# strip.net
KiCad netlist of a schematic drawn in EAGLE
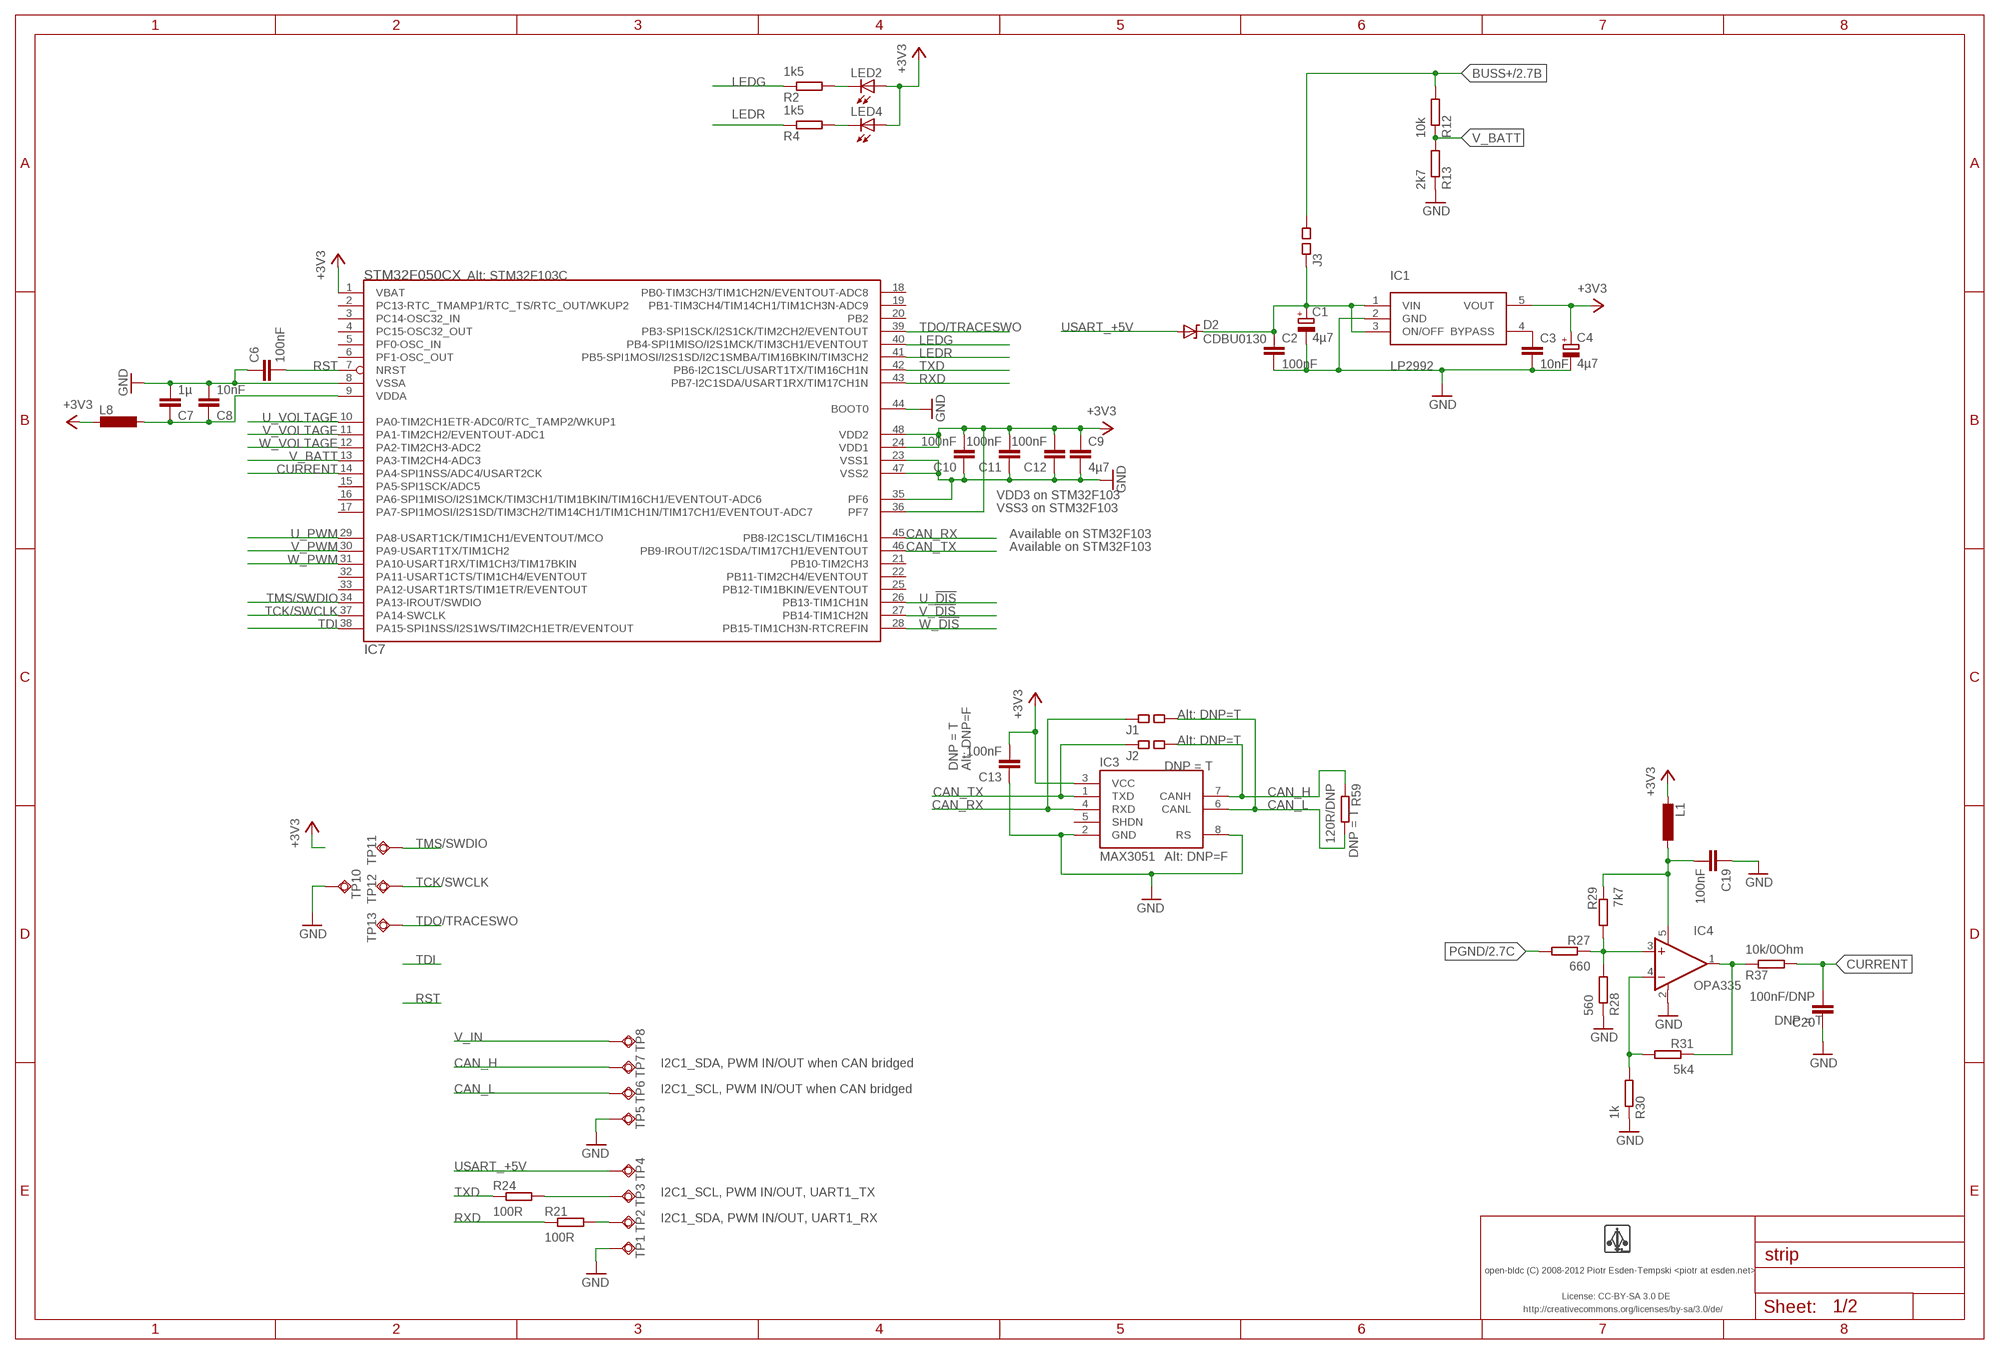
[diagram p0: schematic, sheet 1]
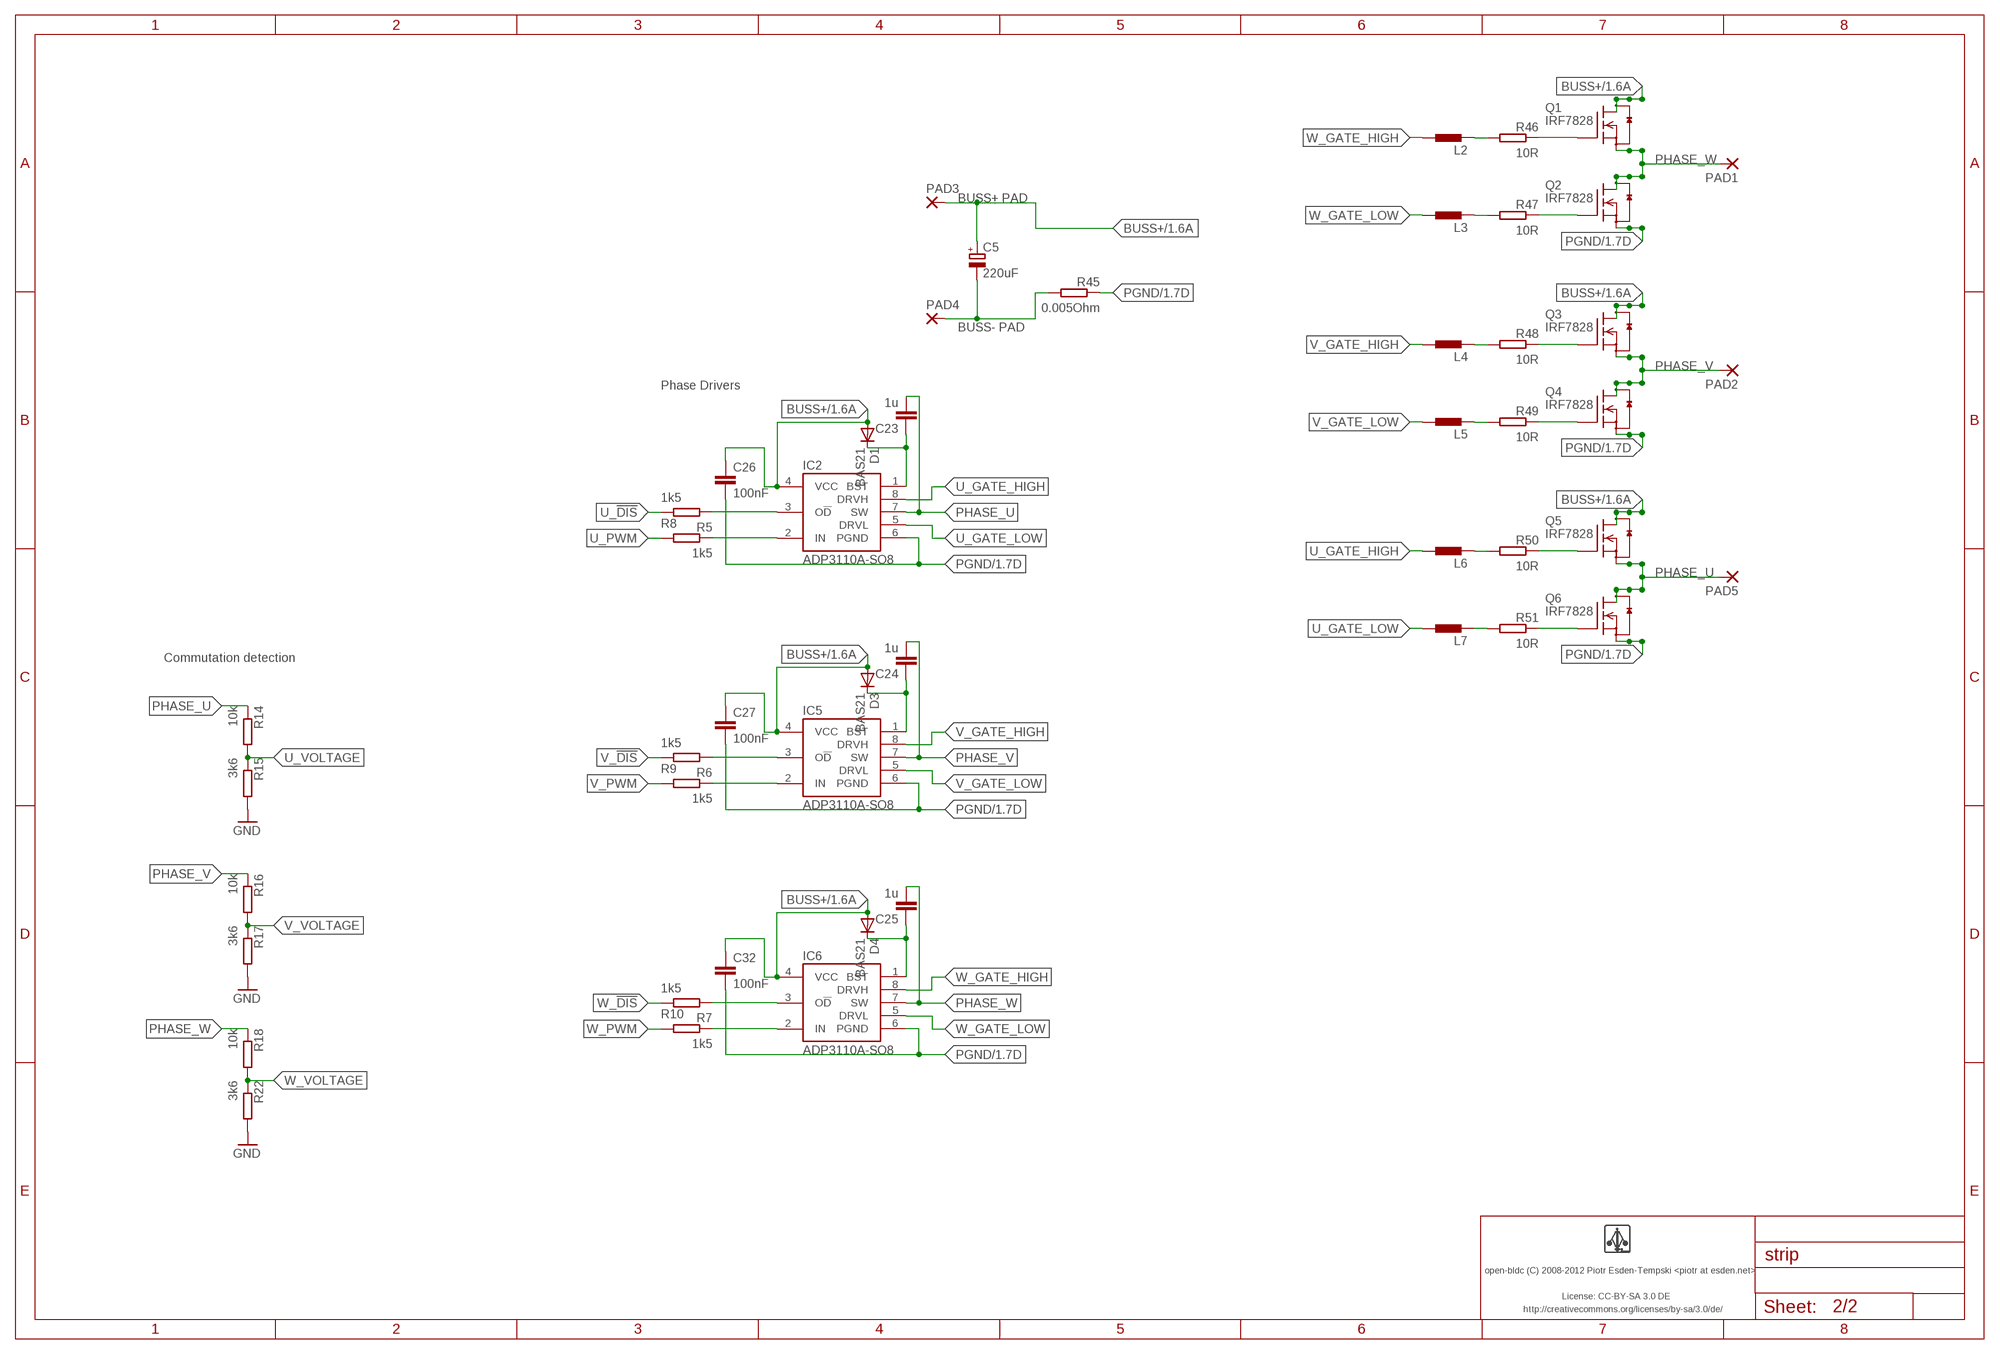
[diagram p1: schematic, sheet 2]

(export (version "E")
  (design (tool "Eeschema 10.0.6"))
  (components
    (comp (ref "C5")
      (value "220uF")
      (footprint "eagle-import:7343_D")
      (fields (field (name "PARTNO") "cap-tan-D-220u-16v"))
      (libsource (lib "eagle-import") (part "CAPACITOR-POLD"))
    )
    (comp (ref "C23")
      (value "1u")
      (footprint "eagle-import:0603-CAP")
      (fields (field (name "PARTNO") "cap-tan-0603-1u"))
      (libsource (lib "eagle-import") (part "CAPACITOR-0603"))
    )
    (comp (ref "C24")
      (value "1u")
      (footprint "eagle-import:0603-CAP")
      (fields (field (name "PARTNO") "cap-tan-0603-1u"))
      (libsource (lib "eagle-import") (part "CAPACITOR-0603"))
    )
    (comp (ref "C25")
      (value "1u")
      (footprint "eagle-import:0603-CAP")
      (fields (field (name "PARTNO") "cap-tan-0603-1u"))
      (libsource (lib "eagle-import") (part "CAPACITOR-0603"))
    )
    (comp (ref "C26")
      (value "100nF")
      (footprint "eagle-import:0402-CAP")
      (fields (field (name "PARTNO") "cap-cer-0402-100n"))
      (libsource (lib "eagle-import") (part "CAPACITOR-0402"))
    )
    (comp (ref "C27")
      (value "100nF")
      (footprint "eagle-import:0402-CAP")
      (fields (field (name "PARTNO") "cap-cer-0402-100n"))
      (libsource (lib "eagle-import") (part "CAPACITOR-0402"))
    )
    (comp (ref "C32")
      (value "100nF")
      (footprint "eagle-import:0402-CAP")
      (fields (field (name "PARTNO") "cap-cer-0402-100n"))
      (libsource (lib "eagle-import") (part "CAPACITOR-0402"))
    )
    (comp (ref "D1")
      (value "BAS21")
      (footprint "eagle-import:SOD-123-DIO")
      (fields (field (name "PARTNO") "diode-sod-123"))
      (libsource (lib "eagle-import") (part "DIODE-SOD-123"))
    )
    (comp (ref "D3")
      (value "BAS21")
      (footprint "eagle-import:SOD-123-DIO")
      (fields (field (name "PARTNO") "diode-sod-123"))
      (libsource (lib "eagle-import") (part "DIODE-SOD-123"))
    )
    (comp (ref "D4")
      (value "BAS21")
      (footprint "eagle-import:SOD-123-DIO")
      (fields (field (name "PARTNO") "diode-sod-123"))
      (libsource (lib "eagle-import") (part "DIODE-SOD-123"))
    )
    (comp (ref "IC2")
      (value "ADP3110A-SO8")
      (footprint "eagle-import:SO8")
      (fields (field (name "PARTNO") "ic-so8-mosfet-driver-buck"))
      (libsource (lib "eagle-import") (part "ADP3110A-SO8"))
    )
    (comp (ref "IC5")
      (value "ADP3110A-SO8")
      (footprint "eagle-import:SO8")
      (fields (field (name "PARTNO") "ic-so8-mosfet-driver-buck"))
      (libsource (lib "eagle-import") (part "ADP3110A-SO8"))
    )
    (comp (ref "IC6")
      (value "ADP3110A-SO8")
      (footprint "eagle-import:SO8")
      (fields (field (name "PARTNO") "ic-so8-mosfet-driver-buck"))
      (libsource (lib "eagle-import") (part "ADP3110A-SO8"))
    )
    (comp (ref "L2")
      (value "INDUCTOR-0402")
      (footprint "eagle-import:0402-IND")
      (fields (field (name "PARTNO") "res-0402-0"))
      (libsource (lib "eagle-import") (part "INDUCTOR-0402"))
    )
    (comp (ref "L3")
      (value "INDUCTOR-0402")
      (footprint "eagle-import:0402-IND")
      (fields (field (name "PARTNO") "res-0402-0"))
      (libsource (lib "eagle-import") (part "INDUCTOR-0402"))
    )
    (comp (ref "L4")
      (value "INDUCTOR-0402")
      (footprint "eagle-import:0402-IND")
      (fields (field (name "PARTNO") "res-0402-0"))
      (libsource (lib "eagle-import") (part "INDUCTOR-0402"))
    )
    (comp (ref "L5")
      (value "INDUCTOR-0402")
      (footprint "eagle-import:0402-IND")
      (fields (field (name "PARTNO") "res-0402-0"))
      (libsource (lib "eagle-import") (part "INDUCTOR-0402"))
    )
    (comp (ref "L6")
      (value "INDUCTOR-0402")
      (footprint "eagle-import:0402-IND")
      (fields (field (name "PARTNO") "res-0402-0"))
      (libsource (lib "eagle-import") (part "INDUCTOR-0402"))
    )
    (comp (ref "L7")
      (value "INDUCTOR-0402")
      (footprint "eagle-import:0402-IND")
      (fields (field (name "PARTNO") "res-0402-0"))
      (libsource (lib "eagle-import") (part "INDUCTOR-0402"))
    )
    (comp (ref "PAD1")
      (value "SMD5")
      (footprint "eagle-import:SMD2,54-5,08")
      (libsource (lib "eagle-import") (part "SMD5"))
    )
    (comp (ref "PAD2")
      (value "SMD5")
      (footprint "eagle-import:SMD2,54-5,08")
      (libsource (lib "eagle-import") (part "SMD5"))
    )
    (comp (ref "PAD3")
      (value "SMD5")
      (footprint "eagle-import:SMD2,54-5,08")
      (libsource (lib "eagle-import") (part "SMD5"))
    )
    (comp (ref "PAD4")
      (value "SMD5")
      (footprint "eagle-import:SMD2,54-5,08")
      (libsource (lib "eagle-import") (part "SMD5"))
    )
    (comp (ref "PAD5")
      (value "SMD5")
      (footprint "eagle-import:SMD2,54-5,08")
      (libsource (lib "eagle-import") (part "SMD5"))
    )
    (comp (ref "Q1")
      (value "IRF7828")
      (footprint "eagle-import:SO8")
      (fields (field (name "PARTNO") "ic-so8-mosfet-n-ch-30v-15a"))
      (libsource (lib "eagle-import") (part "IRF7828"))
    )
    (comp (ref "Q2")
      (value "IRF7828")
      (footprint "eagle-import:SO8")
      (fields (field (name "PARTNO") "ic-so8-mosfet-n-ch-30v-15a"))
      (libsource (lib "eagle-import") (part "IRF7828"))
    )
    (comp (ref "Q3")
      (value "IRF7828")
      (footprint "eagle-import:SO8")
      (fields (field (name "PARTNO") "ic-so8-mosfet-n-ch-30v-15a"))
      (libsource (lib "eagle-import") (part "IRF7828"))
    )
    (comp (ref "Q4")
      (value "IRF7828")
      (footprint "eagle-import:SO8")
      (fields (field (name "PARTNO") "ic-so8-mosfet-n-ch-30v-15a"))
      (libsource (lib "eagle-import") (part "IRF7828"))
    )
    (comp (ref "Q5")
      (value "IRF7828")
      (footprint "eagle-import:SO8")
      (fields (field (name "PARTNO") "ic-so8-mosfet-n-ch-30v-15a"))
      (libsource (lib "eagle-import") (part "IRF7828"))
    )
    (comp (ref "Q6")
      (value "IRF7828")
      (footprint "eagle-import:SO8")
      (fields (field (name "PARTNO") "ic-so8-mosfet-n-ch-30v-15a"))
      (libsource (lib "eagle-import") (part "IRF7828"))
    )
    (comp (ref "R5")
      (value "1k5")
      (footprint "eagle-import:0402-RES")
      (fields (field (name "PARTNO") "res-0402-1k5"))
      (libsource (lib "eagle-import") (part "RESISTOR-0402"))
    )
    (comp (ref "R6")
      (value "1k5")
      (footprint "eagle-import:0402-RES")
      (fields (field (name "PARTNO") "res-0402-1k5"))
      (libsource (lib "eagle-import") (part "RESISTOR-0402"))
    )
    (comp (ref "R7")
      (value "1k5")
      (footprint "eagle-import:0402-RES")
      (fields (field (name "PARTNO") "res-0402-1k5"))
      (libsource (lib "eagle-import") (part "RESISTOR-0402"))
    )
    (comp (ref "R8")
      (value "1k5")
      (footprint "eagle-import:0402-RES")
      (fields (field (name "PARTNO") "res-0402-1k5"))
      (libsource (lib "eagle-import") (part "RESISTOR-0402"))
    )
    (comp (ref "R9")
      (value "1k5")
      (footprint "eagle-import:0402-RES")
      (fields (field (name "PARTNO") "res-0402-1k5"))
      (libsource (lib "eagle-import") (part "RESISTOR-0402"))
    )
    (comp (ref "R10")
      (value "1k5")
      (footprint "eagle-import:0402-RES")
      (fields (field (name "PARTNO") "res-0402-1k5"))
      (libsource (lib "eagle-import") (part "RESISTOR-0402"))
    )
    (comp (ref "R14")
      (value "10k")
      (footprint "eagle-import:0402-RES")
      (fields (field (name "PARTNO") "res-0402-10k"))
      (libsource (lib "eagle-import") (part "RESISTOR-0402"))
    )
    (comp (ref "R15")
      (value "3k6")
      (footprint "eagle-import:0402-RES")
      (fields (field (name "PARTNO") "res-0402-3k6"))
      (libsource (lib "eagle-import") (part "RESISTOR-0402"))
    )
    (comp (ref "R16")
      (value "10k")
      (footprint "eagle-import:0402-RES")
      (fields (field (name "PARTNO") "res-0402-10k"))
      (libsource (lib "eagle-import") (part "RESISTOR-0402"))
    )
    (comp (ref "R17")
      (value "3k6")
      (footprint "eagle-import:0402-RES")
      (fields (field (name "PARTNO") "res-0402-3k6"))
      (libsource (lib "eagle-import") (part "RESISTOR-0402"))
    )
    (comp (ref "R18")
      (value "10k")
      (footprint "eagle-import:0402-RES")
      (fields (field (name "PARTNO") "res-0402-10k"))
      (libsource (lib "eagle-import") (part "RESISTOR-0402"))
    )
    (comp (ref "R22")
      (value "3k6")
      (footprint "eagle-import:0402-RES")
      (fields (field (name "PARTNO") "res-0402-3k6"))
      (libsource (lib "eagle-import") (part "RESISTOR-0402"))
    )
    (comp (ref "R45")
      (value "0.005Ohm")
      (footprint "eagle-import:1206-RES")
      (fields (field (name "PARTNO") "res-1206-0005"))
      (libsource (lib "eagle-import") (part "RESISTOR-1206"))
    )
    (comp (ref "R46")
      (value "10R")
      (footprint "eagle-import:0402-RES")
      (fields (field (name "PARTNO") "res-0402-10"))
      (libsource (lib "eagle-import") (part "RESISTOR-0402"))
    )
    (comp (ref "R47")
      (value "10R")
      (footprint "eagle-import:0402-RES")
      (fields (field (name "PARTNO") "res-0402-10"))
      (libsource (lib "eagle-import") (part "RESISTOR-0402"))
    )
    (comp (ref "R48")
      (value "10R")
      (footprint "eagle-import:0402-RES")
      (fields (field (name "PARTNO") "res-0402-10"))
      (libsource (lib "eagle-import") (part "RESISTOR-0402"))
    )
    (comp (ref "R49")
      (value "10R")
      (footprint "eagle-import:0402-RES")
      (fields (field (name "PARTNO") "res-0402-10"))
      (libsource (lib "eagle-import") (part "RESISTOR-0402"))
    )
    (comp (ref "R50")
      (value "10R")
      (footprint "eagle-import:0402-RES")
      (fields (field (name "PARTNO") "res-0402-10"))
      (libsource (lib "eagle-import") (part "RESISTOR-0402"))
    )
    (comp (ref "R51")
      (value "10R")
      (footprint "eagle-import:0402-RES")
      (fields (field (name "PARTNO") "res-0402-10"))
      (libsource (lib "eagle-import") (part "RESISTOR-0402"))
    )
    (comp (ref "U$2")
      (value "LOGO")
      (footprint "eagle-import:LOGO_SILK_SMALL")
      (libsource (lib "eagle-import") (part "LOGO-SILK-SMALL"))
    )
    (comp (ref "C1")
      (value "4µ7")
      (footprint "eagle-import:0805-POL-CAP")
      (fields (field (name "PARTNO") "cap-cer-0805-4u7-16v"))
      (libsource (lib "eagle-import") (part "CAPACITOR-POL-0805"))
    )
    (comp (ref "C2")
      (value "100nF")
      (footprint "eagle-import:0402-CAP")
      (fields (field (name "PARTNO") "cap-cer-0402-100n"))
      (libsource (lib "eagle-import") (part "CAPACITOR-0402"))
    )
    (comp (ref "C3")
      (value "10nF")
      (footprint "eagle-import:0402-CAP")
      (fields (field (name "PARTNO") "cap-cer-0402-10n"))
      (libsource (lib "eagle-import") (part "CAPACITOR-0402"))
    )
    (comp (ref "C4")
      (value "4µ7")
      (footprint "eagle-import:0805-POL-CAP")
      (fields (field (name "PARTNO") "cap-cer-0805-4u7-16v"))
      (libsource (lib "eagle-import") (part "CAPACITOR-POL-0805"))
    )
    (comp (ref "C6")
      (value "100nF")
      (footprint "eagle-import:0402-CAP")
      (fields (field (name "PARTNO") "cap-cer-0402-100n"))
      (libsource (lib "eagle-import") (part "CAPACITOR-0402"))
    )
    (comp (ref "C7")
      (value "1µ")
      (footprint "eagle-import:0402-CAP")
      (fields (field (name "PARTNO") "cap-cer-0402-1u"))
      (libsource (lib "eagle-import") (part "CAPACITOR-0402"))
    )
    (comp (ref "C8")
      (value "10nF")
      (footprint "eagle-import:0402-CAP")
      (fields (field (name "PARTNO") "cap-cer-0402-10n"))
      (libsource (lib "eagle-import") (part "CAPACITOR-0402"))
    )
    (comp (ref "C9")
      (value "4µ7")
      (footprint "eagle-import:0805-CAP")
      (fields (field (name "PARTNO") "cap-cer-0805-4u7"))
      (libsource (lib "eagle-import") (part "CAPACITOR-0805"))
    )
    (comp (ref "C10")
      (value "100nF")
      (footprint "eagle-import:0402-CAP")
      (fields (field (name "PARTNO") "cap-cer-0402-100n"))
      (libsource (lib "eagle-import") (part "CAPACITOR-0402"))
    )
    (comp (ref "C11")
      (value "100nF")
      (footprint "eagle-import:0402-CAP")
      (fields (field (name "PARTNO") "cap-cer-0402-100n"))
      (libsource (lib "eagle-import") (part "CAPACITOR-0402"))
    )
    (comp (ref "C12")
      (value "100nF")
      (footprint "eagle-import:0402-CAP")
      (fields (field (name "PARTNO") "cap-cer-0402-100n"))
      (libsource (lib "eagle-import") (part "CAPACITOR-0402"))
    )
    (comp (ref "C13")
      (value "100nF")
      (footprint "eagle-import:0402-CAP")
      (fields (field (name "DNP") "T") (field (name "PARTNO") "cap-cer-0402-100n"))
      (libsource (lib "eagle-import") (part "CAPACITOR-0402"))
    )
    (comp (ref "C19")
      (value "100nF")
      (footprint "eagle-import:0402-CAP")
      (fields (field (name "PARTNO") "cap-cer-0402-100n"))
      (libsource (lib "eagle-import") (part "CAPACITOR-0402"))
    )
    (comp (ref "C20")
      (value "100nF/DNP")
      (footprint "eagle-import:0402-CAP")
      (fields (field (name "DNP") "T") (field (name "PARTNO") "cap-cer-0402-100n"))
      (libsource (lib "eagle-import") (part "CAPACITOR-0402"))
    )
    (comp (ref "D2")
      (value "CDBU0130")
      (footprint "eagle-import:0603-DIO")
      (fields (field (name "PARTNO") "diode-0603"))
      (libsource (lib "eagle-import") (part "DIODE-ZENER-0603"))
    )
    (comp (ref "IC1")
      (value "LP2992")
      (footprint "eagle-import:SOT23-5")
      (fields (field (name "PARTNO") "vreg-sot-23-5-3v3"))
      (libsource (lib "eagle-import") (part "LP2992"))
    )
    (comp (ref "IC3")
      (value "MAX3051")
      (footprint "eagle-import:SO8")
      (fields (field (name "DNP") "T") (field (name "PARTNO") "ic-so8-can-3v3"))
      (libsource (lib "eagle-import") (part "MAX3051"))
    )
    (comp (ref "IC4")
      (value "OPA335")
      (footprint "eagle-import:SOT23-5")
      (fields (field (name "PARTNO") "ic-sot-23-5-opamp"))
      (libsource (lib "eagle-import") (part "OPA335"))
    )
    (comp (ref "IC7")
      (value "STM32F050CX")
      (footprint "eagle-import:LQFP48")
      (fields (field (name "PARTNO") "mcu-lqfp-48-stm32f05"))
      (libsource (lib "eagle-import") (part "STM32F050CX"))
    )
    (comp (ref "J1")
      (value "SQ_JMP-0402")
      (footprint "eagle-import:0402-SQJMP")
      (fields (field (name "PARTNO") "res-0402-0"))
      (libsource (lib "eagle-import") (part "SQ_JMP-0402"))
    )
    (comp (ref "J2")
      (value "SQ_JMP-0402")
      (footprint "eagle-import:0402-SQJMP")
      (fields (field (name "PARTNO") "res-0402-0"))
      (libsource (lib "eagle-import") (part "SQ_JMP-0402"))
    )
    (comp (ref "J3")
      (value "SQ_JMP-0402")
      (footprint "eagle-import:0402-SQJMP")
      (fields (field (name "PARTNO") "res-0402-0"))
      (libsource (lib "eagle-import") (part "SQ_JMP-0402"))
    )
    (comp (ref "L1")
      (value "INDUCTOR-0603")
      (footprint "eagle-import:0603-IND")
      (fields (field (name "PARTNO") "ferrite-0603-600ohm"))
      (libsource (lib "eagle-import") (part "res_cap_INDUCTOR-0603"))
    )
    (comp (ref "L8")
      (value "INDUCTOR-0603")
      (footprint "eagle-import:0603-IND")
      (fields (field (name "PARTNO") "ferrite-0603-600ohm"))
      (libsource (lib "eagle-import") (part "res_cap_INDUCTOR-0603"))
    )
    (comp (ref "LED2")
      (value "GREEN")
      (footprint "eagle-import:0402-LED")
      (fields (field (name "PARTNO") "led-0402-green"))
      (libsource (lib "eagle-import") (part "LED-0402"))
    )
    (comp (ref "LED4")
      (value "RED")
      (footprint "eagle-import:0402-LED")
      (fields (field (name "PARTNO") "led-0402-green"))
      (libsource (lib "eagle-import") (part "LED-0402"))
    )
    (comp (ref "R2")
      (value "1k5")
      (footprint "eagle-import:0402-RES")
      (fields (field (name "PARTNO") "res-0402-1k5"))
      (libsource (lib "eagle-import") (part "RESISTOR-0402"))
    )
    (comp (ref "R4")
      (value "1k5")
      (footprint "eagle-import:0402-RES")
      (fields (field (name "PARTNO") "res-0402-1k5"))
      (libsource (lib "eagle-import") (part "RESISTOR-0402"))
    )
    (comp (ref "R12")
      (value "10k")
      (footprint "eagle-import:0402-RES")
      (fields (field (name "PARTNO") "res-0402-10k"))
      (libsource (lib "eagle-import") (part "RESISTOR-0402"))
    )
    (comp (ref "R13")
      (value "2k7")
      (footprint "eagle-import:0402-RES")
      (fields (field (name "PARTNO") "res-0402-2k7"))
      (libsource (lib "eagle-import") (part "RESISTOR-0402"))
    )
    (comp (ref "R21")
      (value "100R")
      (footprint "eagle-import:0402-RES")
      (fields (field (name "PARTNO") "res-0402-100"))
      (libsource (lib "eagle-import") (part "RESISTOR-0402"))
    )
    (comp (ref "R24")
      (value "100R")
      (footprint "eagle-import:0402-RES")
      (fields (field (name "PARTNO") "res-0402-100"))
      (libsource (lib "eagle-import") (part "RESISTOR-0402"))
    )
    (comp (ref "R27")
      (value "660")
      (footprint "eagle-import:0402-RES")
      (fields (field (name "PARTNO") "res-0402-665"))
      (libsource (lib "eagle-import") (part "RESISTOR-0402"))
    )
    (comp (ref "R28")
      (value "560")
      (footprint "eagle-import:0402-RES")
      (fields (field (name "PARTNO") "res-0402-560"))
      (libsource (lib "eagle-import") (part "RESISTOR-0402"))
    )
    (comp (ref "R29")
      (value "7k7")
      (footprint "eagle-import:0402-RES")
      (fields (field (name "PARTNO") "res-0402-7k68"))
      (libsource (lib "eagle-import") (part "RESISTOR-0402"))
    )
    (comp (ref "R30")
      (value "1k")
      (footprint "eagle-import:0402-RES")
      (fields (field (name "PARTNO") "res-0402-1k"))
      (libsource (lib "eagle-import") (part "RESISTOR-0402"))
    )
    (comp (ref "R31")
      (value "5k4")
      (footprint "eagle-import:0402-RES")
      (fields (field (name "PARTNO") "res-0402-5k36"))
      (libsource (lib "eagle-import") (part "RESISTOR-0402"))
    )
    (comp (ref "R37")
      (value "10k/0Ohm")
      (footprint "eagle-import:0402-RES")
      (fields (field (name "PARTNO") "res-0402-0"))
      (libsource (lib "eagle-import") (part "RESISTOR-0402"))
    )
    (comp (ref "R59")
      (value "120R/DNP")
      (footprint "eagle-import:0402-RES")
      (fields (field (name "DNP") "T") (field (name "PARTNO") "res-0402-60.4"))
      (libsource (lib "eagle-import") (part "RESISTOR-0402"))
    )
    (comp (ref "TP1")
      (value "TPSQTP20SQ")
      (footprint "eagle-import:TP20SQ")
      (libsource (lib "eagle-import") (part "TPSQTP20SQ"))
    )
    (comp (ref "TP2")
      (value "TPSQTP20SQ")
      (footprint "eagle-import:TP20SQ")
      (libsource (lib "eagle-import") (part "TPSQTP20SQ"))
    )
    (comp (ref "TP3")
      (value "TPSQTP20SQ")
      (footprint "eagle-import:TP20SQ")
      (libsource (lib "eagle-import") (part "TPSQTP20SQ"))
    )
    (comp (ref "TP4")
      (value "TPSQTP20SQ")
      (footprint "eagle-import:TP20SQ")
      (libsource (lib "eagle-import") (part "TPSQTP20SQ"))
    )
    (comp (ref "TP5")
      (value "TPSQTP20SQ")
      (footprint "eagle-import:TP20SQ")
      (libsource (lib "eagle-import") (part "TPSQTP20SQ"))
    )
    (comp (ref "TP6")
      (value "TPSQTP20SQ")
      (footprint "eagle-import:TP20SQ")
      (libsource (lib "eagle-import") (part "TPSQTP20SQ"))
    )
    (comp (ref "TP7")
      (value "TPSQTP20SQ")
      (footprint "eagle-import:TP20SQ")
      (libsource (lib "eagle-import") (part "TPSQTP20SQ"))
    )
    (comp (ref "TP8")
      (value "TPSQTP20SQ")
      (footprint "eagle-import:TP20SQ")
      (libsource (lib "eagle-import") (part "TPSQTP20SQ"))
    )
    (comp (ref "TP10")
      (value "TPSQTP11SQ")
      (footprint "eagle-import:TP11SQ")
      (libsource (lib "eagle-import") (part "TPSQTP11SQ"))
    )
    (comp (ref "TP11")
      (value "TPSQTP11SQ")
      (footprint "eagle-import:TP11SQ")
      (libsource (lib "eagle-import") (part "TPSQTP11SQ"))
    )
    (comp (ref "TP12")
      (value "TPSQTP11SQ")
      (footprint "eagle-import:TP11SQ")
      (libsource (lib "eagle-import") (part "TPSQTP11SQ"))
    )
    (comp (ref "TP13")
      (value "TPSQTP11SQ")
      (footprint "eagle-import:TP11SQ")
      (libsource (lib "eagle-import") (part "TPSQTP11SQ"))
    )
    (comp (ref "U$1")
      (value "LOGO")
      (footprint "eagle-import:LOGO_SILK_SMALL")
      (libsource (lib "eagle-import") (part "LOGO-SILK-SMALL"))
    )
  )
  (nets
    (net (code "1") (name "+3V3") (class "Default")
      (node (ref "C10") (pin "P$2") (pinfunction "2_P$2") (pintype "passive"))
      (node (ref "C11") (pin "P$2") (pinfunction "2_P$2") (pintype "passive"))
      (node (ref "C12") (pin "P$2") (pinfunction "2_P$2") (pintype "passive"))
      (node (ref "C13") (pin "P$2") (pinfunction "2_P$2") (pintype "passive"))
      (node (ref "C4") (pin "+") (pinfunction "+_+") (pintype "passive"))
      (node (ref "C9") (pin "P$1") (pinfunction "1_P$1") (pintype "passive"))
      (node (ref "IC1") (pin "5") (pinfunction "VOUT_5") (pintype "bidirectional"))
      (node (ref "IC3") (pin "3") (pinfunction "VCC_3") (pintype "bidirectional"))
      (node (ref "IC7") (pin "1") (pinfunction "VBAT_1") (pintype "power_in"))
      (node (ref "IC7") (pin "24") (pinfunction "VDD1_24") (pintype "power_in"))
      (node (ref "IC7") (pin "36") (pinfunction "PF7_36") (pintype "power_in"))
      (node (ref "IC7") (pin "48") (pinfunction "VDD2_48") (pintype "power_in"))
      (node (ref "L1") (pin "P$2") (pinfunction "2_P$2") (pintype "passive"))
      (node (ref "L8") (pin "P$2") (pinfunction "2_P$2") (pintype "passive"))
      (node (ref "LED2") (pin "A") (pinfunction "A_A") (pintype "passive"))
      (node (ref "LED4") (pin "A") (pinfunction "A_A") (pintype "passive"))
    )
    (net (code "2") (name "BUSS+") (class "Default")
      (node (ref "C26") (pin "P$1") (pinfunction "1_P$1") (pintype "passive"))
      (node (ref "C27") (pin "P$1") (pinfunction "1_P$1") (pintype "passive"))
      (node (ref "C32") (pin "P$1") (pinfunction "1_P$1") (pintype "passive"))
      (node (ref "C5") (pin "+") (pinfunction "+_+") (pintype "passive"))
      (node (ref "D1") (pin "A") (pinfunction "A_A") (pintype "passive"))
      (node (ref "D3") (pin "A") (pinfunction "A_A") (pintype "passive"))
      (node (ref "D4") (pin "A") (pinfunction "A_A") (pintype "passive"))
      (node (ref "IC2") (pin "4") (pinfunction "VCC_4") (pintype "bidirectional"))
      (node (ref "IC5") (pin "4") (pinfunction "VCC_4") (pintype "bidirectional"))
      (node (ref "IC6") (pin "4") (pinfunction "VCC_4") (pintype "bidirectional"))
      (node (ref "J3") (pin "P$2") (pinfunction "2_P$2") (pintype "passive"))
      (node (ref "PAD3") (pin "1") (pinfunction "P_1") (pintype "passive"))
      (node (ref "Q1") (pin "5") (pinfunction "D1_5") (pintype "passive"))
      (node (ref "Q1") (pin "6") (pinfunction "D2_6") (pintype "passive"))
      (node (ref "Q1") (pin "7") (pinfunction "D3_7") (pintype "passive"))
      (node (ref "Q1") (pin "8") (pinfunction "D4_8") (pintype "passive"))
      (node (ref "Q3") (pin "5") (pinfunction "D1_5") (pintype "passive"))
      (node (ref "Q3") (pin "6") (pinfunction "D2_6") (pintype "passive"))
      (node (ref "Q3") (pin "7") (pinfunction "D3_7") (pintype "passive"))
      (node (ref "Q3") (pin "8") (pinfunction "D4_8") (pintype "passive"))
      (node (ref "Q5") (pin "5") (pinfunction "D1_5") (pintype "passive"))
      (node (ref "Q5") (pin "6") (pinfunction "D2_6") (pintype "passive"))
      (node (ref "Q5") (pin "7") (pinfunction "D3_7") (pintype "passive"))
      (node (ref "Q5") (pin "8") (pinfunction "D4_8") (pintype "passive"))
      (node (ref "R12") (pin "P$2") (pinfunction "2_P$2") (pintype "passive"))
    )
    (net (code "3") (name "CAN_H") (class "Default")
      (node (ref "IC3") (pin "7") (pinfunction "CANH_7") (pintype "bidirectional"))
      (node (ref "J2") (pin "P$2") (pinfunction "2_P$2") (pintype "passive"))
      (node (ref "R59") (pin "P$1") (pinfunction "1_P$1") (pintype "passive"))
      (node (ref "TP7") (pin "TP") (pinfunction "TP_TP") (pintype "input"))
    )
    (net (code "4") (name "CAN_L") (class "Default")
      (node (ref "IC3") (pin "6") (pinfunction "CANL_6") (pintype "bidirectional"))
      (node (ref "J1") (pin "P$2") (pinfunction "2_P$2") (pintype "passive"))
      (node (ref "R59") (pin "P$2") (pinfunction "2_P$2") (pintype "passive"))
      (node (ref "TP6") (pin "TP") (pinfunction "TP_TP") (pintype "input"))
    )
    (net (code "5") (name "CAN_RX") (class "Default")
      (node (ref "IC3") (pin "4") (pinfunction "RXD_4") (pintype "bidirectional"))
      (node (ref "IC7") (pin "45") (pinfunction "PB8-I2C1SCL/TIM16CH1_45") (pintype "bidirectional"))
      (node (ref "J1") (pin "P$1") (pinfunction "1_P$1") (pintype "passive"))
    )
    (net (code "6") (name "CAN_TX") (class "Default")
      (node (ref "IC3") (pin "1") (pinfunction "TXD_1") (pintype "bidirectional"))
      (node (ref "IC7") (pin "46") (pinfunction "PB9-IROUT/I2C1SDA/TIM17CH1/EVENTOUT_46") (pintype "bidirectional"))
      (node (ref "J2") (pin "P$1") (pinfunction "1_P$1") (pintype "passive"))
    )
    (net (code "7") (name "CURRENT") (class "Default")
      (node (ref "C20") (pin "P$2") (pinfunction "2_P$2") (pintype "passive"))
      (node (ref "IC7") (pin "14") (pinfunction "PA4-SPI1NSS/ADC4/USART2CK_14") (pintype "bidirectional"))
      (node (ref "R37") (pin "P$2") (pinfunction "2_P$2") (pintype "passive"))
    )
    (net (code "8") (name "GND") (class "Default")
      (node (ref "C1") (pin "-") (pinfunction "-_-") (pintype "passive"))
      (node (ref "C10") (pin "P$1") (pinfunction "1_P$1") (pintype "passive"))
      (node (ref "C11") (pin "P$1") (pinfunction "1_P$1") (pintype "passive"))
      (node (ref "C12") (pin "P$1") (pinfunction "1_P$1") (pintype "passive"))
      (node (ref "C13") (pin "P$1") (pinfunction "1_P$1") (pintype "passive"))
      (node (ref "C19") (pin "P$1") (pinfunction "1_P$1") (pintype "passive"))
      (node (ref "C2") (pin "P$2") (pinfunction "2_P$2") (pintype "passive"))
      (node (ref "C20") (pin "P$1") (pinfunction "1_P$1") (pintype "passive"))
      (node (ref "C3") (pin "P$2") (pinfunction "2_P$2") (pintype "passive"))
      (node (ref "C4") (pin "-") (pinfunction "-_-") (pintype "passive"))
      (node (ref "C5") (pin "-") (pinfunction "-_-") (pintype "passive"))
      (node (ref "C6") (pin "P$1") (pinfunction "1_P$1") (pintype "passive"))
      (node (ref "C7") (pin "P$2") (pinfunction "2_P$2") (pintype "passive"))
      (node (ref "C8") (pin "P$2") (pinfunction "2_P$2") (pintype "passive"))
      (node (ref "C9") (pin "P$2") (pinfunction "2_P$2") (pintype "passive"))
      (node (ref "IC1") (pin "2") (pinfunction "GND_2") (pintype "bidirectional"))
      (node (ref "IC3") (pin "2") (pinfunction "GND_2") (pintype "bidirectional"))
      (node (ref "IC3") (pin "8") (pinfunction "RS_8") (pintype "bidirectional"))
      (node (ref "IC4") (pin "2") (pinfunction "V-_2") (pintype "power_in"))
      (node (ref "IC7") (pin "23") (pinfunction "VSS1_23") (pintype "power_in"))
      (node (ref "IC7") (pin "35") (pinfunction "PF6_35") (pintype "power_in"))
      (node (ref "IC7") (pin "44") (pinfunction "BOOT0_44") (pintype "input"))
      (node (ref "IC7") (pin "47") (pinfunction "VSS2_47") (pintype "power_in"))
      (node (ref "IC7") (pin "8") (pinfunction "VSSA_8") (pintype "power_in"))
      (node (ref "PAD4") (pin "1") (pinfunction "P_1") (pintype "passive"))
      (node (ref "R13") (pin "P$1") (pinfunction "1_P$1") (pintype "passive"))
      (node (ref "R15") (pin "P$2") (pinfunction "2_P$2") (pintype "passive"))
      (node (ref "R17") (pin "P$2") (pinfunction "2_P$2") (pintype "passive"))
      (node (ref "R22") (pin "P$2") (pinfunction "2_P$2") (pintype "passive"))
      (node (ref "R28") (pin "P$1") (pinfunction "1_P$1") (pintype "passive"))
      (node (ref "R30") (pin "P$1") (pinfunction "1_P$1") (pintype "passive"))
      (node (ref "R45") (pin "P$2") (pinfunction "2_P$2") (pintype "passive"))
      (node (ref "TP1") (pin "TP") (pinfunction "TP_TP") (pintype "input"))
      (node (ref "TP10") (pin "TP") (pinfunction "TP_TP") (pintype "input"))
      (node (ref "TP5") (pin "TP") (pinfunction "TP_TP") (pintype "input"))
    )
    (net (code "9") (name "LEDG") (class "Default")
      (node (ref "IC7") (pin "40") (pinfunction "PB4-SPI1MISO/I2S1MCK/TIM3CH1/EVENTOUT_40") (pintype "bidirectional"))
      (node (ref "R2") (pin "P$1") (pinfunction "1_P$1") (pintype "passive"))
    )
    (net (code "10") (name "LEDR") (class "Default")
      (node (ref "IC7") (pin "41") (pinfunction "PB5-SPI1MOSI/I2S1SD/I2C1SMBA/TIM16BKIN/TIM3CH2_41") (pintype "bidirectional"))
      (node (ref "R4") (pin "P$1") (pinfunction "1_P$1") (pintype "passive"))
    )
    (net (code "11") (name "Net-(C3-1)") (class "Default")
      (node (ref "C3") (pin "P$1") (pinfunction "1_P$1") (pintype "passive"))
      (node (ref "IC1") (pin "4") (pinfunction "BYPASS_4") (pintype "bidirectional"))
    )
    (net (code "12") (name "Net-(C7-1)") (class "Default")
      (node (ref "C7") (pin "P$1") (pinfunction "1_P$1") (pintype "passive"))
      (node (ref "C8") (pin "P$1") (pinfunction "1_P$1") (pintype "passive"))
      (node (ref "IC7") (pin "9") (pinfunction "VDDA_9") (pintype "power_in"))
      (node (ref "L8") (pin "P$1") (pinfunction "1_P$1") (pintype "passive"))
    )
    (net (code "13") (name "Net-(C19-2)") (class "Default")
      (node (ref "C19") (pin "P$2") (pinfunction "2_P$2") (pintype "passive"))
      (node (ref "IC4") (pin "5") (pinfunction "V+_5") (pintype "power_in"))
      (node (ref "L1") (pin "P$1") (pinfunction "1_P$1") (pintype "passive"))
      (node (ref "R29") (pin "P$1") (pinfunction "1_P$1") (pintype "passive"))
    )
    (net (code "14") (name "Net-(C23-1)") (class "Default")
      (node (ref "C23") (pin "P$1") (pinfunction "1_P$1") (pintype "passive"))
      (node (ref "D1") (pin "C") (pinfunction "C_C") (pintype "passive"))
      (node (ref "IC2") (pin "1") (pinfunction "BST_1") (pintype "bidirectional"))
    )
    (net (code "15") (name "Net-(C24-1)") (class "Default")
      (node (ref "C24") (pin "P$1") (pinfunction "1_P$1") (pintype "passive"))
      (node (ref "D3") (pin "C") (pinfunction "C_C") (pintype "passive"))
      (node (ref "IC5") (pin "1") (pinfunction "BST_1") (pintype "bidirectional"))
    )
    (net (code "16") (name "Net-(C25-1)") (class "Default")
      (node (ref "C25") (pin "P$1") (pinfunction "1_P$1") (pintype "passive"))
      (node (ref "D4") (pin "C") (pinfunction "C_C") (pintype "passive"))
      (node (ref "IC6") (pin "1") (pinfunction "BST_1") (pintype "bidirectional"))
    )
    (net (code "17") (name "Net-(IC2-IN)") (class "Default")
      (node (ref "IC2") (pin "2") (pinfunction "IN_2") (pintype "bidirectional"))
      (node (ref "R5") (pin "P$1") (pinfunction "1_P$1") (pintype "passive"))
    )
    (net (code "18") (name "Net-(IC2-O~{D})") (class "Default")
      (node (ref "IC2") (pin "3") (pinfunction "O~{D}_3") (pintype "bidirectional"))
      (node (ref "R8") (pin "P$2") (pinfunction "2_P$2") (pintype "passive"))
    )
    (net (code "19") (name "Net-(IC4-+IN)") (class "Default")
      (node (ref "IC4") (pin "3") (pinfunction "+IN_3") (pintype "input"))
      (node (ref "R27") (pin "P$1") (pinfunction "1_P$1") (pintype "passive"))
      (node (ref "R28") (pin "P$2") (pinfunction "2_P$2") (pintype "passive"))
      (node (ref "R29") (pin "P$2") (pinfunction "2_P$2") (pintype "passive"))
    )
    (net (code "20") (name "Net-(IC4--IN)") (class "Default")
      (node (ref "IC4") (pin "4") (pinfunction "-IN_4") (pintype "input"))
      (node (ref "R30") (pin "P$2") (pinfunction "2_P$2") (pintype "passive"))
      (node (ref "R31") (pin "P$2") (pinfunction "2_P$2") (pintype "passive"))
    )
    (net (code "21") (name "Net-(IC4-OUT)") (class "Default")
      (node (ref "IC4") (pin "1") (pinfunction "OUT_1") (pintype "output"))
      (node (ref "R31") (pin "P$1") (pinfunction "1_P$1") (pintype "passive"))
      (node (ref "R37") (pin "P$1") (pinfunction "1_P$1") (pintype "passive"))
    )
    (net (code "22") (name "Net-(IC5-IN)") (class "Default")
      (node (ref "IC5") (pin "2") (pinfunction "IN_2") (pintype "bidirectional"))
      (node (ref "R6") (pin "P$1") (pinfunction "1_P$1") (pintype "passive"))
    )
    (net (code "23") (name "Net-(IC5-O~{D})") (class "Default")
      (node (ref "IC5") (pin "3") (pinfunction "O~{D}_3") (pintype "bidirectional"))
      (node (ref "R9") (pin "P$2") (pinfunction "2_P$2") (pintype "passive"))
    )
    (net (code "24") (name "Net-(IC6-IN)") (class "Default")
      (node (ref "IC6") (pin "2") (pinfunction "IN_2") (pintype "bidirectional"))
      (node (ref "R7") (pin "P$1") (pinfunction "1_P$1") (pintype "passive"))
    )
    (net (code "25") (name "Net-(IC6-O~{D})") (class "Default")
      (node (ref "IC6") (pin "3") (pinfunction "O~{D}_3") (pintype "bidirectional"))
      (node (ref "R10") (pin "P$2") (pinfunction "2_P$2") (pintype "passive"))
    )
    (net (code "26") (name "Net-(L2-2)") (class "Default")
      (node (ref "L2") (pin "P$2") (pinfunction "2_P$2") (pintype "passive"))
      (node (ref "R46") (pin "P$2") (pinfunction "2_P$2") (pintype "passive"))
    )
    (net (code "27") (name "Net-(L3-2)") (class "Default")
      (node (ref "L3") (pin "P$2") (pinfunction "2_P$2") (pintype "passive"))
      (node (ref "R47") (pin "P$2") (pinfunction "2_P$2") (pintype "passive"))
    )
    (net (code "28") (name "Net-(L4-2)") (class "Default")
      (node (ref "L4") (pin "P$2") (pinfunction "2_P$2") (pintype "passive"))
      (node (ref "R48") (pin "P$2") (pinfunction "2_P$2") (pintype "passive"))
    )
    (net (code "29") (name "Net-(L5-2)") (class "Default")
      (node (ref "L5") (pin "P$2") (pinfunction "2_P$2") (pintype "passive"))
      (node (ref "R49") (pin "P$2") (pinfunction "2_P$2") (pintype "passive"))
    )
    (net (code "30") (name "Net-(L6-2)") (class "Default")
      (node (ref "L6") (pin "P$2") (pinfunction "2_P$2") (pintype "passive"))
      (node (ref "R50") (pin "P$2") (pinfunction "2_P$2") (pintype "passive"))
    )
    (net (code "31") (name "Net-(L7-2)") (class "Default")
      (node (ref "L7") (pin "P$2") (pinfunction "2_P$2") (pintype "passive"))
      (node (ref "R51") (pin "P$2") (pinfunction "2_P$2") (pintype "passive"))
    )
    (net (code "32") (name "Net-(Q1-G)") (class "Default")
      (node (ref "Q1") (pin "4") (pinfunction "G_4") (pintype "passive"))
      (node (ref "R46") (pin "P$1") (pinfunction "1_P$1") (pintype "passive"))
    )
    (net (code "33") (name "Net-(Q2-G)") (class "Default")
      (node (ref "Q2") (pin "4") (pinfunction "G_4") (pintype "passive"))
      (node (ref "R47") (pin "P$1") (pinfunction "1_P$1") (pintype "passive"))
    )
    (net (code "34") (name "Net-(Q3-G)") (class "Default")
      (node (ref "Q3") (pin "4") (pinfunction "G_4") (pintype "passive"))
      (node (ref "R48") (pin "P$1") (pinfunction "1_P$1") (pintype "passive"))
    )
    (net (code "35") (name "Net-(Q4-G)") (class "Default")
      (node (ref "Q4") (pin "4") (pinfunction "G_4") (pintype "passive"))
      (node (ref "R49") (pin "P$1") (pinfunction "1_P$1") (pintype "passive"))
    )
    (net (code "36") (name "Net-(Q5-G)") (class "Default")
      (node (ref "Q5") (pin "4") (pinfunction "G_4") (pintype "passive"))
      (node (ref "R50") (pin "P$1") (pinfunction "1_P$1") (pintype "passive"))
    )
    (net (code "37") (name "Net-(Q6-G)") (class "Default")
      (node (ref "Q6") (pin "4") (pinfunction "G_4") (pintype "passive"))
      (node (ref "R51") (pin "P$1") (pinfunction "1_P$1") (pintype "passive"))
    )
    (net (code "38") (name "Net-(R2-2)") (class "Default")
      (node (ref "LED2") (pin "C") (pinfunction "C_C") (pintype "passive"))
      (node (ref "R2") (pin "P$2") (pinfunction "2_P$2") (pintype "passive"))
    )
    (net (code "39") (name "Net-(R4-2)") (class "Default")
      (node (ref "LED4") (pin "C") (pinfunction "C_C") (pintype "passive"))
      (node (ref "R4") (pin "P$2") (pinfunction "2_P$2") (pintype "passive"))
    )
    (net (code "40") (name "Net-(R21-2)") (class "Default")
      (node (ref "R21") (pin "P$2") (pinfunction "2_P$2") (pintype "passive"))
      (node (ref "TP2") (pin "TP") (pinfunction "TP_TP") (pintype "input"))
    )
    (net (code "41") (name "Net-(R24-2)") (class "Default")
      (node (ref "R24") (pin "P$2") (pinfunction "2_P$2") (pintype "passive"))
      (node (ref "TP3") (pin "TP") (pinfunction "TP_TP") (pintype "input"))
    )
    (net (code "42") (name "PGND") (class "Default")
      (node (ref "C26") (pin "P$2") (pinfunction "2_P$2") (pintype "passive"))
      (node (ref "C27") (pin "P$2") (pinfunction "2_P$2") (pintype "passive"))
      (node (ref "C32") (pin "P$2") (pinfunction "2_P$2") (pintype "passive"))
      (node (ref "IC2") (pin "6") (pinfunction "PGND_6") (pintype "bidirectional"))
      (node (ref "IC5") (pin "6") (pinfunction "PGND_6") (pintype "bidirectional"))
      (node (ref "IC6") (pin "6") (pinfunction "PGND_6") (pintype "bidirectional"))
      (node (ref "Q2") (pin "1") (pinfunction "S3_1") (pintype "passive"))
      (node (ref "Q2") (pin "2") (pinfunction "S2_2") (pintype "passive"))
      (node (ref "Q2") (pin "3") (pinfunction "S1_3") (pintype "passive"))
      (node (ref "Q4") (pin "1") (pinfunction "S3_1") (pintype "passive"))
      (node (ref "Q4") (pin "2") (pinfunction "S2_2") (pintype "passive"))
      (node (ref "Q4") (pin "3") (pinfunction "S1_3") (pintype "passive"))
      (node (ref "Q6") (pin "1") (pinfunction "S3_1") (pintype "passive"))
      (node (ref "Q6") (pin "2") (pinfunction "S2_2") (pintype "passive"))
      (node (ref "Q6") (pin "3") (pinfunction "S1_3") (pintype "passive"))
      (node (ref "R27") (pin "P$2") (pinfunction "2_P$2") (pintype "passive"))
      (node (ref "R45") (pin "P$1") (pinfunction "1_P$1") (pintype "passive"))
    )
    (net (code "43") (name "PHASE_U") (class "Default")
      (node (ref "C23") (pin "P$2") (pinfunction "2_P$2") (pintype "passive"))
      (node (ref "IC2") (pin "7") (pinfunction "SW_7") (pintype "bidirectional"))
      (node (ref "PAD5") (pin "1") (pinfunction "P_1") (pintype "passive"))
      (node (ref "Q5") (pin "1") (pinfunction "S3_1") (pintype "passive"))
      (node (ref "Q5") (pin "2") (pinfunction "S2_2") (pintype "passive"))
      (node (ref "Q5") (pin "3") (pinfunction "S1_3") (pintype "passive"))
      (node (ref "Q6") (pin "5") (pinfunction "D1_5") (pintype "passive"))
      (node (ref "Q6") (pin "6") (pinfunction "D2_6") (pintype "passive"))
      (node (ref "Q6") (pin "7") (pinfunction "D3_7") (pintype "passive"))
      (node (ref "Q6") (pin "8") (pinfunction "D4_8") (pintype "passive"))
      (node (ref "R14") (pin "P$1") (pinfunction "1_P$1") (pintype "passive"))
    )
    (net (code "44") (name "PHASE_V") (class "Default")
      (node (ref "C24") (pin "P$2") (pinfunction "2_P$2") (pintype "passive"))
      (node (ref "IC5") (pin "7") (pinfunction "SW_7") (pintype "bidirectional"))
      (node (ref "PAD2") (pin "1") (pinfunction "P_1") (pintype "passive"))
      (node (ref "Q3") (pin "1") (pinfunction "S3_1") (pintype "passive"))
      (node (ref "Q3") (pin "2") (pinfunction "S2_2") (pintype "passive"))
      (node (ref "Q3") (pin "3") (pinfunction "S1_3") (pintype "passive"))
      (node (ref "Q4") (pin "5") (pinfunction "D1_5") (pintype "passive"))
      (node (ref "Q4") (pin "6") (pinfunction "D2_6") (pintype "passive"))
      (node (ref "Q4") (pin "7") (pinfunction "D3_7") (pintype "passive"))
      (node (ref "Q4") (pin "8") (pinfunction "D4_8") (pintype "passive"))
      (node (ref "R16") (pin "P$1") (pinfunction "1_P$1") (pintype "passive"))
    )
    (net (code "45") (name "PHASE_W") (class "Default")
      (node (ref "C25") (pin "P$2") (pinfunction "2_P$2") (pintype "passive"))
      (node (ref "IC6") (pin "7") (pinfunction "SW_7") (pintype "bidirectional"))
      (node (ref "PAD1") (pin "1") (pinfunction "P_1") (pintype "passive"))
      (node (ref "Q1") (pin "1") (pinfunction "S3_1") (pintype "passive"))
      (node (ref "Q1") (pin "2") (pinfunction "S2_2") (pintype "passive"))
      (node (ref "Q1") (pin "3") (pinfunction "S1_3") (pintype "passive"))
      (node (ref "Q2") (pin "5") (pinfunction "D1_5") (pintype "passive"))
      (node (ref "Q2") (pin "6") (pinfunction "D2_6") (pintype "passive"))
      (node (ref "Q2") (pin "7") (pinfunction "D3_7") (pintype "passive"))
      (node (ref "Q2") (pin "8") (pinfunction "D4_8") (pintype "passive"))
      (node (ref "R18") (pin "P$1") (pinfunction "1_P$1") (pintype "passive"))
    )
    (net (code "46") (name "RST") (class "Default")
      (node (ref "C6") (pin "P$2") (pinfunction "2_P$2") (pintype "passive"))
      (node (ref "IC7") (pin "7") (pinfunction "NRST_7") (pintype "bidirectional"))
    )
    (net (code "47") (name "RXD") (class "Default")
      (node (ref "IC7") (pin "43") (pinfunction "PB7-I2C1SDA/USART1RX/TIM17CH1N_43") (pintype "bidirectional"))
      (node (ref "R21") (pin "P$1") (pinfunction "1_P$1") (pintype "passive"))
    )
    (net (code "48") (name "TCK{slash}SWCLK") (class "Default")
      (node (ref "IC7") (pin "37") (pinfunction "PA14-SWCLK_37") (pintype "bidirectional"))
      (node (ref "TP12") (pin "TP") (pinfunction "TP_TP") (pintype "input"))
    )
    (net (code "49") (name "TDI") (class "Default")
      (node (ref "IC7") (pin "38") (pinfunction "PA15-SPI1NSS/I2S1WS/TIM2CH1ETR/EVENTOUT_38") (pintype "bidirectional"))
    )
    (net (code "50") (name "TDO{slash}TRACESWO") (class "Default")
      (node (ref "IC7") (pin "39") (pinfunction "PB3-SPI1SCK/I2S1CK/TIM2CH2/EVENTOUT_39") (pintype "bidirectional"))
      (node (ref "TP13") (pin "TP") (pinfunction "TP_TP") (pintype "input"))
    )
    (net (code "51") (name "TMS{slash}SWDIO") (class "Default")
      (node (ref "IC7") (pin "34") (pinfunction "PA13-IROUT/SWDIO_34") (pintype "bidirectional"))
      (node (ref "TP11") (pin "TP") (pinfunction "TP_TP") (pintype "input"))
    )
    (net (code "52") (name "TXD") (class "Default")
      (node (ref "IC7") (pin "42") (pinfunction "PB6-I2C1SCL/USART1TX/TIM16CH1N_42") (pintype "bidirectional"))
      (node (ref "R24") (pin "P$1") (pinfunction "1_P$1") (pintype "passive"))
    )
    (net (code "53") (name "USART_+5V") (class "Default")
      (node (ref "D2") (pin "A") (pinfunction "A_A") (pintype "passive"))
      (node (ref "TP4") (pin "TP") (pinfunction "TP_TP") (pintype "input"))
    )
    (net (code "54") (name "U_GATE_HIGH") (class "Default")
      (node (ref "IC2") (pin "8") (pinfunction "DRVH_8") (pintype "bidirectional"))
      (node (ref "L6") (pin "P$1") (pinfunction "1_P$1") (pintype "passive"))
    )
    (net (code "55") (name "U_GATE_LOW") (class "Default")
      (node (ref "IC2") (pin "5") (pinfunction "DRVL_5") (pintype "bidirectional"))
      (node (ref "L7") (pin "P$1") (pinfunction "1_P$1") (pintype "passive"))
    )
    (net (code "56") (name "U_PWM") (class "Default")
      (node (ref "IC7") (pin "29") (pinfunction "PA8-USART1CK/TIM1CH1/EVENTOUT/MCO_29") (pintype "bidirectional"))
      (node (ref "R5") (pin "P$2") (pinfunction "2_P$2") (pintype "passive"))
    )
    (net (code "57") (name "U_VOLTAGE") (class "Default")
      (node (ref "IC7") (pin "10") (pinfunction "PA0-TIM2CH1ETR-ADC0/RTC_TAMP2/WKUP1_10") (pintype "bidirectional"))
      (node (ref "R14") (pin "P$2") (pinfunction "2_P$2") (pintype "passive"))
      (node (ref "R15") (pin "P$1") (pinfunction "1_P$1") (pintype "passive"))
    )
    (net (code "58") (name "U_~{DIS}") (class "Default")
      (node (ref "IC7") (pin "26") (pinfunction "PB13-TIM1CH1N_26") (pintype "bidirectional"))
      (node (ref "R8") (pin "P$1") (pinfunction "1_P$1") (pintype "passive"))
    )
    (net (code "59") (name "V_BATT") (class "Default")
      (node (ref "IC7") (pin "13") (pinfunction "PA3-TIM2CH4-ADC3_13") (pintype "bidirectional"))
      (node (ref "R12") (pin "P$1") (pinfunction "1_P$1") (pintype "passive"))
      (node (ref "R13") (pin "P$2") (pinfunction "2_P$2") (pintype "passive"))
    )
    (net (code "60") (name "V_GATE_HIGH") (class "Default")
      (node (ref "IC5") (pin "8") (pinfunction "DRVH_8") (pintype "bidirectional"))
      (node (ref "L4") (pin "P$1") (pinfunction "1_P$1") (pintype "passive"))
    )
    (net (code "61") (name "V_GATE_LOW") (class "Default")
      (node (ref "IC5") (pin "5") (pinfunction "DRVL_5") (pintype "bidirectional"))
      (node (ref "L5") (pin "P$1") (pinfunction "1_P$1") (pintype "passive"))
    )
    (net (code "62") (name "V_IN") (class "Default")
      (node (ref "C1") (pin "+") (pinfunction "+_+") (pintype "passive"))
      (node (ref "C2") (pin "P$1") (pinfunction "1_P$1") (pintype "passive"))
      (node (ref "D2") (pin "C") (pinfunction "C_C") (pintype "passive"))
      (node (ref "IC1") (pin "1") (pinfunction "VIN_1") (pintype "bidirectional"))
      (node (ref "IC1") (pin "3") (pinfunction "ON/OFF_3") (pintype "bidirectional"))
      (node (ref "J3") (pin "P$1") (pinfunction "1_P$1") (pintype "passive"))
      (node (ref "TP8") (pin "TP") (pinfunction "TP_TP") (pintype "input"))
    )
    (net (code "63") (name "V_PWM") (class "Default")
      (node (ref "IC7") (pin "30") (pinfunction "PA9-USART1TX/TIM1CH2_30") (pintype "bidirectional"))
      (node (ref "R6") (pin "P$2") (pinfunction "2_P$2") (pintype "passive"))
    )
    (net (code "64") (name "V_VOLTAGE") (class "Default")
      (node (ref "IC7") (pin "11") (pinfunction "PA1-TIM2CH2/EVENTOUT-ADC1_11") (pintype "bidirectional"))
      (node (ref "R16") (pin "P$2") (pinfunction "2_P$2") (pintype "passive"))
      (node (ref "R17") (pin "P$1") (pinfunction "1_P$1") (pintype "passive"))
    )
    (net (code "65") (name "V_~{DIS}") (class "Default")
      (node (ref "IC7") (pin "27") (pinfunction "PB14-TIM1CH2N_27") (pintype "bidirectional"))
      (node (ref "R9") (pin "P$1") (pinfunction "1_P$1") (pintype "passive"))
    )
    (net (code "66") (name "W_GATE_HIGH") (class "Default")
      (node (ref "IC6") (pin "8") (pinfunction "DRVH_8") (pintype "bidirectional"))
      (node (ref "L2") (pin "P$1") (pinfunction "1_P$1") (pintype "passive"))
    )
    (net (code "67") (name "W_GATE_LOW") (class "Default")
      (node (ref "IC6") (pin "5") (pinfunction "DRVL_5") (pintype "bidirectional"))
      (node (ref "L3") (pin "P$1") (pinfunction "1_P$1") (pintype "passive"))
    )
    (net (code "68") (name "W_PWM") (class "Default")
      (node (ref "IC7") (pin "31") (pinfunction "PA10-USART1RX/TIM1CH3/TIM17BKIN_31") (pintype "bidirectional"))
      (node (ref "R7") (pin "P$2") (pinfunction "2_P$2") (pintype "passive"))
    )
    (net (code "69") (name "W_VOLTAGE") (class "Default")
      (node (ref "IC7") (pin "12") (pinfunction "PA2-TIM2CH3-ADC2_12") (pintype "bidirectional"))
      (node (ref "R18") (pin "P$2") (pinfunction "2_P$2") (pintype "passive"))
      (node (ref "R22") (pin "P$1") (pinfunction "1_P$1") (pintype "passive"))
    )
    (net (code "70") (name "W_~{DIS}") (class "Default")
      (node (ref "IC7") (pin "28") (pinfunction "PB15-TIM1CH3N-RTCREFIN_28") (pintype "bidirectional"))
      (node (ref "R10") (pin "P$1") (pinfunction "1_P$1") (pintype "passive"))
    )
    (net (code "71") (name "unconnected-(IC3-SHDN-Pad5)") (class "Default")
      (node (ref "IC3") (pin "5") (pinfunction "SHDN_5") (pintype "bidirectional"))
    )
    (net (code "72") (name "unconnected-(IC7-PA5-SPI1SCK{slash}ADC5-Pad15)") (class "Default")
      (node (ref "IC7") (pin "15") (pinfunction "PA5-SPI1SCK/ADC5_15") (pintype "bidirectional"))
    )
    (net (code "73") (name "unconnected-(IC7-PA6-SPI1MISO{slash}I2S1MCK{slash}TIM3CH1{slash}TIM1BKIN{slash}TIM16CH1{slash}EVENTOUT-ADC6-Pad16)") (class "Default")
      (node (ref "IC7") (pin "16") (pinfunction "PA6-SPI1MISO/I2S1MCK/TIM3CH1/TIM1BKIN/TIM16CH1/EVENTOUT-ADC6_16") (pintype "bidirectional"))
    )
    (net (code "74") (name "unconnected-(IC7-PA7-SPI1MOSI{slash}I2S1SD{slash}TIM3CH2{slash}TIM14CH1{slash}TIM1CH1N{slash}TIM17CH1{slash}EVENTOUT-ADC7-Pad17)") (class "Default")
      (node (ref "IC7") (pin "17") (pinfunction "PA7-SPI1MOSI/I2S1SD/TIM3CH2/TIM14CH1/TIM1CH1N/TIM17CH1/EVENTOUT-ADC7_17") (pintype "bidirectional"))
    )
    (net (code "75") (name "unconnected-(IC7-PA11-USART1CTS{slash}TIM1CH4{slash}EVENTOUT-Pad32)") (class "Default")
      (node (ref "IC7") (pin "32") (pinfunction "PA11-USART1CTS/TIM1CH4/EVENTOUT_32") (pintype "bidirectional"))
    )
    (net (code "76") (name "unconnected-(IC7-PA12-USART1RTS{slash}TIM1ETR{slash}EVENTOUT-Pad33)") (class "Default")
      (node (ref "IC7") (pin "33") (pinfunction "PA12-USART1RTS/TIM1ETR/EVENTOUT_33") (pintype "bidirectional"))
    )
    (net (code "77") (name "unconnected-(IC7-PB0-TIM3CH3{slash}TIM1CH2N{slash}EVENTOUT-ADC8-Pad18)") (class "Default")
      (node (ref "IC7") (pin "18") (pinfunction "PB0-TIM3CH3/TIM1CH2N/EVENTOUT-ADC8_18") (pintype "bidirectional"))
    )
    (net (code "78") (name "unconnected-(IC7-PB1-TIM3CH4{slash}TIM14CH1{slash}TIM1CH3N-ADC9-Pad19)") (class "Default")
      (node (ref "IC7") (pin "19") (pinfunction "PB1-TIM3CH4/TIM14CH1/TIM1CH3N-ADC9_19") (pintype "bidirectional"))
    )
    (net (code "79") (name "unconnected-(IC7-PB2-Pad20)") (class "Default")
      (node (ref "IC7") (pin "20") (pinfunction "PB2_20") (pintype "bidirectional"))
    )
    (net (code "80") (name "unconnected-(IC7-PB10-TIM2CH3-Pad21)") (class "Default")
      (node (ref "IC7") (pin "21") (pinfunction "PB10-TIM2CH3_21") (pintype "bidirectional"))
    )
    (net (code "81") (name "unconnected-(IC7-PB11-TIM2CH4{slash}EVENTOUT-Pad22)") (class "Default")
      (node (ref "IC7") (pin "22") (pinfunction "PB11-TIM2CH4/EVENTOUT_22") (pintype "bidirectional"))
    )
    (net (code "82") (name "unconnected-(IC7-PB12-TIM1BKIN{slash}EVENTOUT-Pad25)") (class "Default")
      (node (ref "IC7") (pin "25") (pinfunction "PB12-TIM1BKIN/EVENTOUT_25") (pintype "bidirectional"))
    )
    (net (code "83") (name "unconnected-(IC7-PC13-RTC_TMAMP1{slash}RTC_TS{slash}RTC_OUT{slash}WKUP2-Pad2)") (class "Default")
      (node (ref "IC7") (pin "2") (pinfunction "PC13-RTC_TMAMP1/RTC_TS/RTC_OUT/WKUP2_2") (pintype "bidirectional"))
    )
    (net (code "84") (name "unconnected-(IC7-PC14-OSC32_IN-Pad3)") (class "Default")
      (node (ref "IC7") (pin "3") (pinfunction "PC14-OSC32_IN_3") (pintype "bidirectional"))
    )
    (net (code "85") (name "unconnected-(IC7-PC15-OSC32_OUT-Pad4)") (class "Default")
      (node (ref "IC7") (pin "4") (pinfunction "PC15-OSC32_OUT_4") (pintype "bidirectional"))
    )
    (net (code "86") (name "unconnected-(IC7-PF0-OSC_IN-Pad5)") (class "Default")
      (node (ref "IC7") (pin "5") (pinfunction "PF0-OSC_IN_5") (pintype "input"))
    )
    (net (code "87") (name "unconnected-(IC7-PF1-OSC_OUT-Pad6)") (class "Default")
      (node (ref "IC7") (pin "6") (pinfunction "PF1-OSC_OUT_6") (pintype "output"))
    )
  )
)
